# Sheet1.net
KiCad netlist of a schematic drawn in Altium Designer
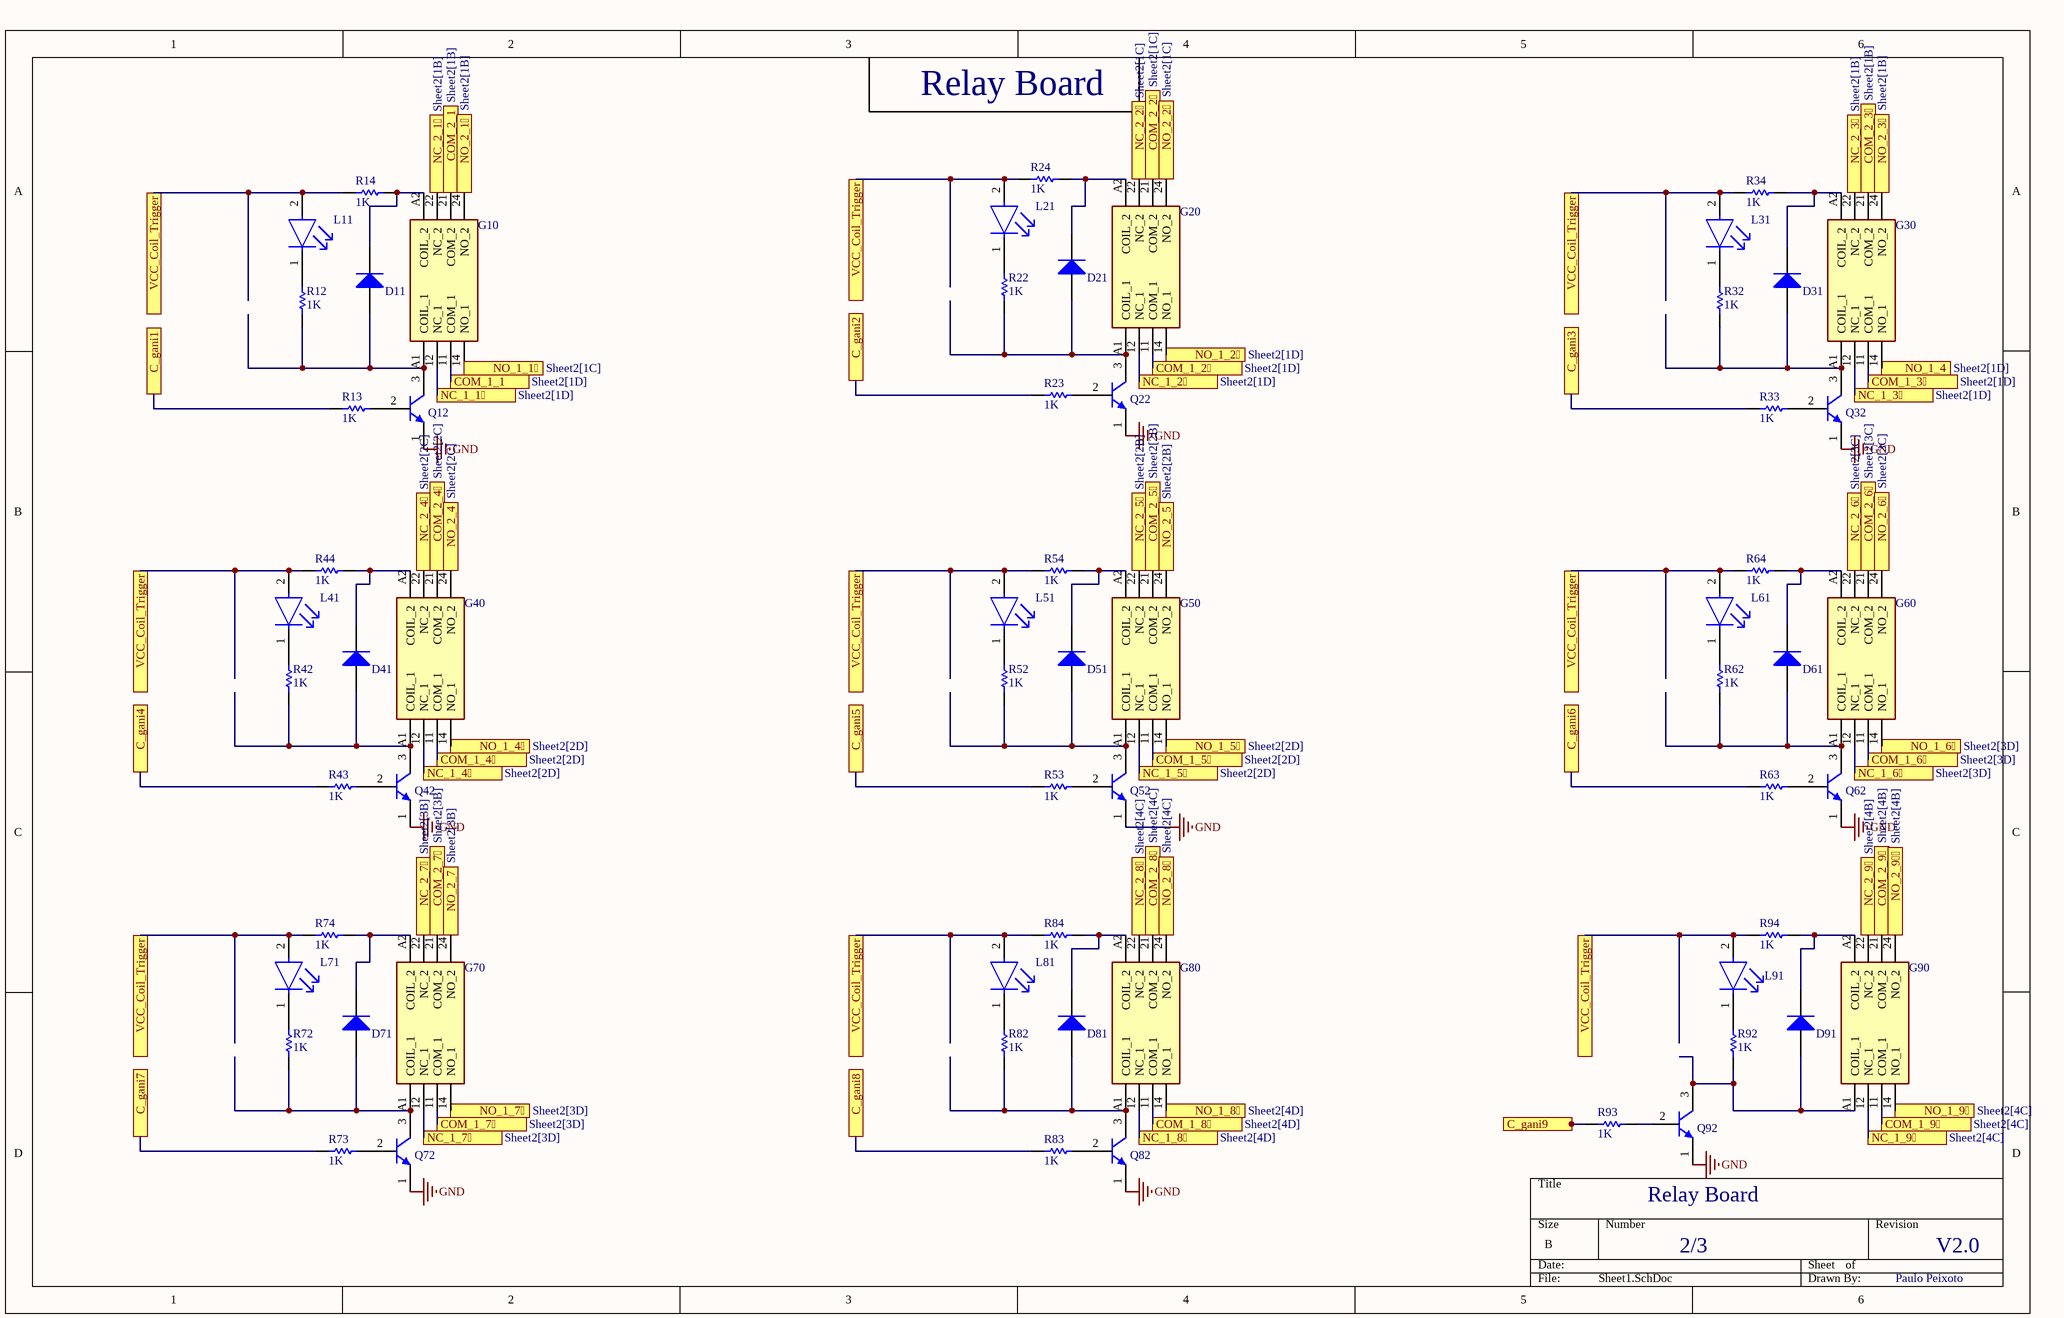
[diagram p0: Sheet1.SchDoc]

(export (version "E")
  (design (tool "Eeschema 10.0.6"))
  (components
    (comp (ref "D11")
      (value "1N4001-T")
      (footprint "DIOD-DO-41-P-2_V")
      (description "1.0 A Rectifier, 15 pF, 50 V, -65 to 150 degC, 2-Pin DO-41 Plastic, RoHS, Tape and Reel")
      (fields (field (name "MANUFACTURER") "Diodes Inc"))
      (libsource (lib "Altium Content Vault") (part "DIOD-D-A1K2-2"))
    )
    (comp (ref "D21")
      (value "1N4001-T")
      (footprint "DIOD-DO-41-P-2_V")
      (description "1.0 A Rectifier, 15 pF, 50 V, -65 to 150 degC, 2-Pin DO-41 Plastic, RoHS, Tape and Reel")
      (fields (field (name "MANUFACTURER") "Diodes Inc"))
      (libsource (lib "Altium Content Vault") (part "DIOD-D-A1K2-2"))
    )
    (comp (ref "D31")
      (value "1N4001-T")
      (footprint "DIOD-DO-41-P-2_V")
      (description "1.0 A Rectifier, 15 pF, 50 V, -65 to 150 degC, 2-Pin DO-41 Plastic, RoHS, Tape and Reel")
      (fields (field (name "MANUFACTURER") "Diodes Inc"))
      (libsource (lib "Altium Content Vault") (part "DIOD-D-A1K2-2"))
    )
    (comp (ref "D41")
      (value "1N4001-T")
      (footprint "DIOD-DO-41-P-2_V")
      (description "1.0 A Rectifier, 15 pF, 50 V, -65 to 150 degC, 2-Pin DO-41 Plastic, RoHS, Tape and Reel")
      (fields (field (name "MANUFACTURER") "Diodes Inc"))
      (libsource (lib "Altium Content Vault") (part "DIOD-D-A1K2-2"))
    )
    (comp (ref "D51")
      (value "1N4001-T")
      (footprint "DIOD-DO-41-P-2_V")
      (description "1.0 A Rectifier, 15 pF, 50 V, -65 to 150 degC, 2-Pin DO-41 Plastic, RoHS, Tape and Reel")
      (fields (field (name "MANUFACTURER") "Diodes Inc"))
      (libsource (lib "Altium Content Vault") (part "DIOD-D-A1K2-2"))
    )
    (comp (ref "D61")
      (value "1N4001-T")
      (footprint "DIOD-DO-41-P-2_V")
      (description "1.0 A Rectifier, 15 pF, 50 V, -65 to 150 degC, 2-Pin DO-41 Plastic, RoHS, Tape and Reel")
      (fields (field (name "MANUFACTURER") "Diodes Inc"))
      (libsource (lib "Altium Content Vault") (part "DIOD-D-A1K2-2"))
    )
    (comp (ref "D71")
      (value "1N4001-T")
      (footprint "DIOD-DO-41-P-2_V")
      (description "1.0 A Rectifier, 15 pF, 50 V, -65 to 150 degC, 2-Pin DO-41 Plastic, RoHS, Tape and Reel")
      (fields (field (name "MANUFACTURER") "Diodes Inc"))
      (libsource (lib "Altium Content Vault") (part "DIOD-D-A1K2-2"))
    )
    (comp (ref "D81")
      (value "1N4001-T")
      (footprint "DIOD-DO-41-P-2_V")
      (description "1.0 A Rectifier, 15 pF, 50 V, -65 to 150 degC, 2-Pin DO-41 Plastic, RoHS, Tape and Reel")
      (fields (field (name "MANUFACTURER") "Diodes Inc"))
      (libsource (lib "Altium Content Vault") (part "DIOD-D-A1K2-2"))
    )
    (comp (ref "D91")
      (value "1N4001-T")
      (footprint "DIOD-DO-41-P-2_V")
      (description "1.0 A Rectifier, 15 pF, 50 V, -65 to 150 degC, 2-Pin DO-41 Plastic, RoHS, Tape and Reel")
      (fields (field (name "MANUFACTURER") "Diodes Inc"))
      (libsource (lib "Altium Content Vault") (part "DIOD-D-A1K2-2"))
    )
    (comp (ref "G10")
      (value "40.52.9.012.0000")
      (footprint "405290120000")
      (description "Relay or Contactor")
      (libsource (lib "GEPE_SchLib_Altium") (part "Relay 40.52.9.012.0000"))
    )
    (comp (ref "G20")
      (value "40.52.9.012.0000")
      (footprint "405290120000")
      (description "Relay or Contactor")
      (libsource (lib "GEPE_SchLib_Altium") (part "Relay 40.52.9.012.0000"))
    )
    (comp (ref "G30")
      (value "40.52.9.012.0000")
      (footprint "405290120000")
      (description "Relay or Contactor")
      (libsource (lib "GEPE_SchLib_Altium") (part "Relay 40.52.9.012.0000"))
    )
    (comp (ref "G40")
      (value "40.52.9.012.0000")
      (footprint "405290120000")
      (description "Relay or Contactor")
      (libsource (lib "GEPE_SchLib_Altium") (part "Relay 40.52.9.012.0000"))
    )
    (comp (ref "G50")
      (value "40.52.9.012.0000")
      (footprint "405290120000")
      (description "Relay or Contactor")
      (libsource (lib "GEPE_SchLib_Altium") (part "Relay 40.52.9.012.0000"))
    )
    (comp (ref "G60")
      (value "40.52.9.012.0000")
      (footprint "405290120000")
      (description "Relay or Contactor")
      (libsource (lib "GEPE_SchLib_Altium") (part "Relay 40.52.9.012.0000"))
    )
    (comp (ref "G70")
      (value "40.52.9.012.0000")
      (footprint "405290120000")
      (description "Relay or Contactor")
      (libsource (lib "GEPE_SchLib_Altium") (part "Relay 40.52.9.012.0000"))
    )
    (comp (ref "G80")
      (value "40.52.9.012.0000")
      (footprint "405290120000")
      (description "Relay or Contactor")
      (libsource (lib "GEPE_SchLib_Altium") (part "Relay 40.52.9.012.0000"))
    )
    (comp (ref "G90")
      (value "40.52.9.012.0000")
      (footprint "405290120000")
      (description "Relay or Contactor")
      (libsource (lib "GEPE_SchLib_Altium") (part "Relay 40.52.9.012.0000"))
    )
    (comp (ref "L11")
      (value "TLLG4400")
      (footprint "FP-6_544-5255_01-4-MFG")
      (description "TLLG4400 Led, Pcb, Green, 0.63MCD, 3MM, T-1, 7MA, 1.9V, 565NM, 25DEG, 20V, 20MW, -40")
      (libsource (lib "Altium Content Vault") (part "8706943c75ba83719d021d2fdc84c58"))
    )
    (comp (ref "L21")
      (value "TLLG4400")
      (footprint "FP-6_544-5255_01-4-MFG")
      (description "TLLG4400 Led, Pcb, Green, 0.63MCD, 3MM, T-1, 7MA, 1.9V, 565NM, 25DEG, 20V, 20MW, -40")
      (libsource (lib "Altium Content Vault") (part "8706943c75ba83719d021d2fdc84c58"))
    )
    (comp (ref "L31")
      (value "TLLG4400")
      (footprint "FP-6_544-5255_01-4-MFG")
      (description "TLLG4400 Led, Pcb, Green, 0.63MCD, 3MM, T-1, 7MA, 1.9V, 565NM, 25DEG, 20V, 20MW, -40")
      (libsource (lib "Altium Content Vault") (part "8706943c75ba83719d021d2fdc84c58"))
    )
    (comp (ref "L41")
      (value "TLLG4400")
      (footprint "FP-6_544-5255_01-4-MFG")
      (description "TLLG4400 Led, Pcb, Green, 0.63MCD, 3MM, T-1, 7MA, 1.9V, 565NM, 25DEG, 20V, 20MW, -40")
      (libsource (lib "Altium Content Vault") (part "8706943c75ba83719d021d2fdc84c58"))
    )
    (comp (ref "L51")
      (value "TLLG4400")
      (footprint "FP-6_544-5255_01-4-MFG")
      (description "TLLG4400 Led, Pcb, Green, 0.63MCD, 3MM, T-1, 7MA, 1.9V, 565NM, 25DEG, 20V, 20MW, -40")
      (libsource (lib "Altium Content Vault") (part "8706943c75ba83719d021d2fdc84c58"))
    )
    (comp (ref "L61")
      (value "TLLG4400")
      (footprint "FP-6_544-5255_01-4-MFG")
      (description "TLLG4400 Led, Pcb, Green, 0.63MCD, 3MM, T-1, 7MA, 1.9V, 565NM, 25DEG, 20V, 20MW, -40")
      (libsource (lib "Altium Content Vault") (part "8706943c75ba83719d021d2fdc84c58"))
    )
    (comp (ref "L71")
      (value "TLLG4400")
      (footprint "FP-6_544-5255_01-4-MFG")
      (description "TLLG4400 Led, Pcb, Green, 0.63MCD, 3MM, T-1, 7MA, 1.9V, 565NM, 25DEG, 20V, 20MW, -40")
      (libsource (lib "Altium Content Vault") (part "8706943c75ba83719d021d2fdc84c58"))
    )
    (comp (ref "L81")
      (value "TLLG4400")
      (footprint "FP-6_544-5255_01-4-MFG")
      (description "TLLG4400 Led, Pcb, Green, 0.63MCD, 3MM, T-1, 7MA, 1.9V, 565NM, 25DEG, 20V, 20MW, -40")
      (libsource (lib "Altium Content Vault") (part "8706943c75ba83719d021d2fdc84c58"))
    )
    (comp (ref "L91")
      (value "TLLG4400")
      (footprint "FP-6_544-5255_01-4-MFG")
      (description "TLLG4400 Led, Pcb, Green, 0.63MCD, 3MM, T-1, 7MA, 1.9V, 565NM, 25DEG, 20V, 20MW, -40")
      (libsource (lib "Altium Content Vault") (part "8706943c75ba83719d021d2fdc84c58"))
    )
    (comp (ref "Q12")
      (value "PN2222ATF")
      (footprint "FAIR-TO-92-3")
      (description "NPN General-Purpose Amplifier, 40 V, -55 to 150 degC, 3-Pin TO-92, RoHS, Tape and Reel")
      (fields (field (name "MANUFACTURER") "FairchildSemiconductor"))
      (libsource (lib "Altium Content Vault") (part "BJT-NPN-EBC-3"))
    )
    (comp (ref "Q22")
      (value "PN2222ATF")
      (footprint "FAIR-TO-92-3")
      (description "NPN General-Purpose Amplifier, 40 V, -55 to 150 degC, 3-Pin TO-92, RoHS, Tape and Reel")
      (fields (field (name "MANUFACTURER") "FairchildSemiconductor"))
      (libsource (lib "Altium Content Vault") (part "BJT-NPN-EBC-3"))
    )
    (comp (ref "Q32")
      (value "PN2222ATF")
      (footprint "FAIR-TO-92-3")
      (description "NPN General-Purpose Amplifier, 40 V, -55 to 150 degC, 3-Pin TO-92, RoHS, Tape and Reel")
      (fields (field (name "MANUFACTURER") "FairchildSemiconductor"))
      (libsource (lib "Altium Content Vault") (part "BJT-NPN-EBC-3"))
    )
    (comp (ref "Q42")
      (value "PN2222ATF")
      (footprint "FAIR-TO-92-3")
      (description "NPN General-Purpose Amplifier, 40 V, -55 to 150 degC, 3-Pin TO-92, RoHS, Tape and Reel")
      (fields (field (name "MANUFACTURER") "FairchildSemiconductor"))
      (libsource (lib "Altium Content Vault") (part "BJT-NPN-EBC-3"))
    )
    (comp (ref "Q52")
      (value "PN2222ATF")
      (footprint "FAIR-TO-92-3")
      (description "NPN General-Purpose Amplifier, 40 V, -55 to 150 degC, 3-Pin TO-92, RoHS, Tape and Reel")
      (fields (field (name "MANUFACTURER") "FairchildSemiconductor"))
      (libsource (lib "Altium Content Vault") (part "BJT-NPN-EBC-3"))
    )
    (comp (ref "Q62")
      (value "PN2222ATF")
      (footprint "FAIR-TO-92-3")
      (description "NPN General-Purpose Amplifier, 40 V, -55 to 150 degC, 3-Pin TO-92, RoHS, Tape and Reel")
      (fields (field (name "MANUFACTURER") "FairchildSemiconductor"))
      (libsource (lib "Altium Content Vault") (part "BJT-NPN-EBC-3"))
    )
    (comp (ref "Q72")
      (value "PN2222ATF")
      (footprint "FAIR-TO-92-3")
      (description "NPN General-Purpose Amplifier, 40 V, -55 to 150 degC, 3-Pin TO-92, RoHS, Tape and Reel")
      (fields (field (name "MANUFACTURER") "FairchildSemiconductor"))
      (libsource (lib "Altium Content Vault") (part "BJT-NPN-EBC-3"))
    )
    (comp (ref "Q82")
      (value "PN2222ATF")
      (footprint "FAIR-TO-92-3")
      (description "NPN General-Purpose Amplifier, 40 V, -55 to 150 degC, 3-Pin TO-92, RoHS, Tape and Reel")
      (fields (field (name "MANUFACTURER") "FairchildSemiconductor"))
      (libsource (lib "Altium Content Vault") (part "BJT-NPN-EBC-3"))
    )
    (comp (ref "Q92")
      (value "PN2222ATF")
      (footprint "FAIR-TO-92-3")
      (description "NPN General-Purpose Amplifier, 40 V, -55 to 150 degC, 3-Pin TO-92, RoHS, Tape and Reel")
      (fields (field (name "MANUFACTURER") "FairchildSemiconductor"))
      (libsource (lib "Altium Content Vault") (part "BJT-NPN-EBC-3"))
    )
    (comp (ref "R12")
      (value "1K")
      (footprint "RESC3216X70X50NL05T20")
      (fields (field (name "MANUFACTURER") "Panasonic") (field (name "PART NUMBER") "ERJ-8GEY0R00V"))
      (libsource (lib "Altium Content Vault") (part "RES"))
    )
    (comp (ref "R13")
      (value "1K")
      (footprint "RESC3216X70X50NL05T20")
      (fields (field (name "MANUFACTURER") "Panasonic") (field (name "PART NUMBER") "ERJ-8GEY0R00V"))
      (libsource (lib "Altium Content Vault") (part "RES"))
    )
    (comp (ref "R14")
      (value "1K")
      (footprint "RESC3216X70X50NL05T20")
      (fields (field (name "MANUFACTURER") "Panasonic") (field (name "PART NUMBER") "ERJ-8GEY0R00V"))
      (libsource (lib "Altium Content Vault") (part "RES"))
    )
    (comp (ref "R22")
      (value "1K")
      (footprint "RESC3216X70X50NL05T20")
      (fields (field (name "MANUFACTURER") "Panasonic") (field (name "PART NUMBER") "ERJ-8GEY0R00V"))
      (libsource (lib "Altium Content Vault") (part "RES"))
    )
    (comp (ref "R23")
      (value "1K")
      (footprint "RESC3216X70X50NL05T20")
      (fields (field (name "MANUFACTURER") "Panasonic") (field (name "PART NUMBER") "ERJ-8GEY0R00V"))
      (libsource (lib "Altium Content Vault") (part "RES"))
    )
    (comp (ref "R24")
      (value "1K")
      (footprint "RESC3216X70X50NL05T20")
      (fields (field (name "MANUFACTURER") "Panasonic") (field (name "PART NUMBER") "ERJ-8GEY0R00V"))
      (libsource (lib "Altium Content Vault") (part "RES"))
    )
    (comp (ref "R32")
      (value "1K")
      (footprint "RESC3216X70X50NL05T20")
      (fields (field (name "MANUFACTURER") "Panasonic") (field (name "PART NUMBER") "ERJ-8GEY0R00V"))
      (libsource (lib "Altium Content Vault") (part "RES"))
    )
    (comp (ref "R33")
      (value "1K")
      (footprint "RESC3216X70X50NL05T20")
      (fields (field (name "MANUFACTURER") "Panasonic") (field (name "PART NUMBER") "ERJ-8GEY0R00V"))
      (libsource (lib "Altium Content Vault") (part "RES"))
    )
    (comp (ref "R34")
      (value "1K")
      (footprint "RESC3216X70X50NL05T20")
      (fields (field (name "MANUFACTURER") "Panasonic") (field (name "PART NUMBER") "ERJ-8GEY0R00V"))
      (libsource (lib "Altium Content Vault") (part "RES"))
    )
    (comp (ref "R42")
      (value "1K")
      (footprint "RESC3216X70X50NL05T20")
      (fields (field (name "MANUFACTURER") "Panasonic") (field (name "PART NUMBER") "ERJ-8GEY0R00V"))
      (libsource (lib "Altium Content Vault") (part "RES"))
    )
    (comp (ref "R43")
      (value "1K")
      (footprint "RESC3216X70X50NL05T20")
      (fields (field (name "MANUFACTURER") "Panasonic") (field (name "PART NUMBER") "ERJ-8GEY0R00V"))
      (libsource (lib "Altium Content Vault") (part "RES"))
    )
    (comp (ref "R44")
      (value "1K")
      (footprint "RESC3216X70X50NL05T20")
      (fields (field (name "MANUFACTURER") "Panasonic") (field (name "PART NUMBER") "ERJ-8GEY0R00V"))
      (libsource (lib "Altium Content Vault") (part "RES"))
    )
    (comp (ref "R52")
      (value "1K")
      (footprint "RESC3216X70X50NL05T20")
      (fields (field (name "MANUFACTURER") "Panasonic") (field (name "PART NUMBER") "ERJ-8GEY0R00V"))
      (libsource (lib "Altium Content Vault") (part "RES"))
    )
    (comp (ref "R53")
      (value "1K")
      (footprint "RESC3216X70X50NL05T20")
      (fields (field (name "MANUFACTURER") "Panasonic") (field (name "PART NUMBER") "ERJ-8GEY0R00V"))
      (libsource (lib "Altium Content Vault") (part "RES"))
    )
    (comp (ref "R54")
      (value "1K")
      (footprint "RESC3216X70X50NL05T20")
      (fields (field (name "MANUFACTURER") "Panasonic") (field (name "PART NUMBER") "ERJ-8GEY0R00V"))
      (libsource (lib "Altium Content Vault") (part "RES"))
    )
    (comp (ref "R62")
      (value "1K")
      (footprint "RESC3216X70X50NL05T20")
      (fields (field (name "MANUFACTURER") "Panasonic") (field (name "PART NUMBER") "ERJ-8GEY0R00V"))
      (libsource (lib "Altium Content Vault") (part "RES"))
    )
    (comp (ref "R63")
      (value "1K")
      (footprint "RESC3216X70X50NL05T20")
      (fields (field (name "MANUFACTURER") "Panasonic") (field (name "PART NUMBER") "ERJ-8GEY0R00V"))
      (libsource (lib "Altium Content Vault") (part "RES"))
    )
    (comp (ref "R64")
      (value "1K")
      (footprint "RESC3216X70X50NL05T20")
      (fields (field (name "MANUFACTURER") "Panasonic") (field (name "PART NUMBER") "ERJ-8GEY0R00V"))
      (libsource (lib "Altium Content Vault") (part "RES"))
    )
    (comp (ref "R72")
      (value "1K")
      (footprint "RESC3216X70X50NL05T20")
      (fields (field (name "MANUFACTURER") "Panasonic") (field (name "PART NUMBER") "ERJ-8GEY0R00V"))
      (libsource (lib "Altium Content Vault") (part "RES"))
    )
    (comp (ref "R73")
      (value "1K")
      (footprint "RESC3216X70X50NL05T20")
      (fields (field (name "MANUFACTURER") "Panasonic") (field (name "PART NUMBER") "ERJ-8GEY0R00V"))
      (libsource (lib "Altium Content Vault") (part "RES"))
    )
    (comp (ref "R74")
      (value "1K")
      (footprint "RESC3216X70X50NL05T20")
      (fields (field (name "MANUFACTURER") "Panasonic") (field (name "PART NUMBER") "ERJ-8GEY0R00V"))
      (libsource (lib "Altium Content Vault") (part "RES"))
    )
    (comp (ref "R82")
      (value "1K")
      (footprint "RESC3216X70X50NL05T20")
      (fields (field (name "MANUFACTURER") "Panasonic") (field (name "PART NUMBER") "ERJ-8GEY0R00V"))
      (libsource (lib "Altium Content Vault") (part "RES"))
    )
    (comp (ref "R83")
      (value "1K")
      (footprint "RESC3216X70X50NL05T20")
      (fields (field (name "MANUFACTURER") "Panasonic") (field (name "PART NUMBER") "ERJ-8GEY0R00V"))
      (libsource (lib "Altium Content Vault") (part "RES"))
    )
    (comp (ref "R84")
      (value "1K")
      (footprint "RESC3216X70X50NL05T20")
      (fields (field (name "MANUFACTURER") "Panasonic") (field (name "PART NUMBER") "ERJ-8GEY0R00V"))
      (libsource (lib "Altium Content Vault") (part "RES"))
    )
    (comp (ref "R92")
      (value "1K")
      (footprint "RESC3216X70X50NL05T20")
      (fields (field (name "MANUFACTURER") "Panasonic") (field (name "PART NUMBER") "ERJ-8GEY0R00V"))
      (libsource (lib "Altium Content Vault") (part "RES"))
    )
    (comp (ref "R93")
      (value "1K")
      (footprint "RESC3216X70X50NL05T20")
      (fields (field (name "MANUFACTURER") "Panasonic") (field (name "PART NUMBER") "ERJ-8GEY0R00V"))
      (libsource (lib "Altium Content Vault") (part "RES"))
    )
    (comp (ref "R94")
      (value "1K")
      (footprint "RESC3216X70X50NL05T20")
      (fields (field (name "MANUFACTURER") "Panasonic") (field (name "PART NUMBER") "ERJ-8GEY0R00V"))
      (libsource (lib "Altium Content Vault") (part "RES"))
    )
  )
  (nets
    (net (code "1") (name "/COM_1_1") (class "Default")
      (node (ref "G10") (pin "11") (pinfunction "COM_1_11") (pintype "passive"))
    )
    (net (code "2") (name "/COM_1_2") (class "Default")
      (node (ref "G20") (pin "11") (pinfunction "COM_1_11") (pintype "passive"))
    )
    (net (code "3") (name "/COM_1_3") (class "Default")
      (node (ref "G30") (pin "11") (pinfunction "COM_1_11") (pintype "passive"))
    )
    (net (code "4") (name "/COM_1_4") (class "Default")
      (node (ref "G40") (pin "11") (pinfunction "COM_1_11") (pintype "passive"))
    )
    (net (code "5") (name "/COM_1_5") (class "Default")
      (node (ref "G50") (pin "11") (pinfunction "COM_1_11") (pintype "passive"))
    )
    (net (code "6") (name "/COM_1_6") (class "Default")
      (node (ref "G60") (pin "11") (pinfunction "COM_1_11") (pintype "passive"))
    )
    (net (code "7") (name "/COM_1_7") (class "Default")
      (node (ref "G70") (pin "11") (pinfunction "COM_1_11") (pintype "passive"))
    )
    (net (code "8") (name "/COM_1_8") (class "Default")
      (node (ref "G80") (pin "11") (pinfunction "COM_1_11") (pintype "passive"))
    )
    (net (code "9") (name "/COM_1_9") (class "Default")
      (node (ref "G90") (pin "11") (pinfunction "COM_1_11") (pintype "passive"))
    )
    (net (code "19") (name "/COM_2_1") (class "Default")
      (node (ref "G10") (pin "21") (pinfunction "COM_2_21") (pintype "passive"))
    )
    (net (code "20") (name "/C_gani1") (class "Default")
      (node (ref "R13") (pin "2") (pinfunction "2_2") (pintype "passive"))
    )
    (net (code "21") (name "/C_gani2") (class "Default")
      (node (ref "R23") (pin "2") (pinfunction "2_2") (pintype "passive"))
    )
    (net (code "22") (name "/C_gani3") (class "Default")
      (node (ref "R33") (pin "2") (pinfunction "2_2") (pintype "passive"))
    )
    (net (code "23") (name "/C_gani4") (class "Default")
      (node (ref "R43") (pin "2") (pinfunction "2_2") (pintype "passive"))
    )
    (net (code "24") (name "/C_gani5") (class "Default")
      (node (ref "R53") (pin "2") (pinfunction "2_2") (pintype "passive"))
    )
    (net (code "25") (name "/C_gani6") (class "Default")
      (node (ref "R63") (pin "2") (pinfunction "2_2") (pintype "passive"))
    )
    (net (code "26") (name "/C_gani7") (class "Default")
      (node (ref "R73") (pin "2") (pinfunction "2_2") (pintype "passive"))
    )
    (net (code "27") (name "/C_gani8") (class "Default")
      (node (ref "R83") (pin "2") (pinfunction "2_2") (pintype "passive"))
    )
    (net (code "28") (name "/C_gani9") (class "Default")
      (node (ref "R93") (pin "2") (pinfunction "2_2") (pintype "passive"))
    )
    (net (code "29") (name "/NC_1_1") (class "Default")
      (node (ref "G10") (pin "12") (pinfunction "NC_1_12") (pintype "passive"))
    )
    (net (code "30") (name "/NC_1_2") (class "Default")
      (node (ref "G20") (pin "12") (pinfunction "NC_1_12") (pintype "passive"))
    )
    (net (code "31") (name "/NC_1_3") (class "Default")
      (node (ref "G30") (pin "12") (pinfunction "NC_1_12") (pintype "passive"))
    )
    (net (code "32") (name "/NC_1_4") (class "Default")
      (node (ref "G40") (pin "12") (pinfunction "NC_1_12") (pintype "passive"))
    )
    (net (code "33") (name "/NC_1_5") (class "Default")
      (node (ref "G50") (pin "12") (pinfunction "NC_1_12") (pintype "passive"))
    )
    (net (code "34") (name "/NC_1_6") (class "Default")
      (node (ref "G60") (pin "12") (pinfunction "NC_1_12") (pintype "passive"))
    )
    (net (code "35") (name "/NC_1_7") (class "Default")
      (node (ref "G70") (pin "12") (pinfunction "NC_1_12") (pintype "passive"))
    )
    (net (code "36") (name "/NC_1_8") (class "Default")
      (node (ref "G80") (pin "12") (pinfunction "NC_1_12") (pintype "passive"))
    )
    (net (code "64") (name "/NC_1_9") (class "Default")
      (node (ref "G90") (pin "12") (pinfunction "NC_1_12") (pintype "passive"))
    )
    (net (code "65") (name "/NO_1_4") (class "Default")
      (node (ref "G30") (pin "14") (pinfunction "NO_1_14") (pintype "passive"))
    )
    (net (code "66") (name "/NO_2_4") (class "Default")
      (node (ref "G40") (pin "24") (pinfunction "NO_2_24") (pintype "passive"))
    )
    (net (code "67") (name "/NO_2_5") (class "Default")
      (node (ref "G50") (pin "24") (pinfunction "NO_2_24") (pintype "passive"))
    )
    (net (code "68") (name "/NO_2_7") (class "Default")
      (node (ref "G70") (pin "24") (pinfunction "NO_2_24") (pintype "passive"))
    )
    (net (code "69") (name "/VCC_Coil_Trigger") (class "Default")
      (node (ref "L11") (pin "2") (pinfunction "A_2") (pintype "passive"))
      (node (ref "L21") (pin "2") (pinfunction "A_2") (pintype "passive"))
      (node (ref "L31") (pin "2") (pinfunction "A_2") (pintype "passive"))
      (node (ref "L41") (pin "2") (pinfunction "A_2") (pintype "passive"))
      (node (ref "L51") (pin "2") (pinfunction "A_2") (pintype "passive"))
      (node (ref "L61") (pin "2") (pinfunction "A_2") (pintype "passive"))
      (node (ref "L71") (pin "2") (pinfunction "A_2") (pintype "passive"))
      (node (ref "L81") (pin "2") (pinfunction "A_2") (pintype "passive"))
      (node (ref "L91") (pin "2") (pinfunction "A_2") (pintype "passive"))
      (node (ref "R14") (pin "1") (pinfunction "1_1") (pintype "passive"))
      (node (ref "R24") (pin "1") (pinfunction "1_1") (pintype "passive"))
      (node (ref "R34") (pin "1") (pinfunction "1_1") (pintype "passive"))
      (node (ref "R44") (pin "1") (pinfunction "1_1") (pintype "passive"))
      (node (ref "R54") (pin "1") (pinfunction "1_1") (pintype "passive"))
      (node (ref "R64") (pin "1") (pinfunction "1_1") (pintype "passive"))
      (node (ref "R74") (pin "1") (pinfunction "1_1") (pintype "passive"))
      (node (ref "R84") (pin "1") (pinfunction "1_1") (pintype "passive"))
      (node (ref "R94") (pin "1") (pinfunction "1_1") (pintype "passive"))
    )
    (net (code "70") (name "GND") (class "Default")
      (node (ref "Q12") (pin "1") (pinfunction "E_1") (pintype "passive"))
      (node (ref "Q22") (pin "1") (pinfunction "E_1") (pintype "passive"))
      (node (ref "Q32") (pin "1") (pinfunction "E_1") (pintype "passive"))
      (node (ref "Q42") (pin "1") (pinfunction "E_1") (pintype "passive"))
      (node (ref "Q52") (pin "1") (pinfunction "E_1") (pintype "passive"))
      (node (ref "Q62") (pin "1") (pinfunction "E_1") (pintype "passive"))
      (node (ref "Q72") (pin "1") (pinfunction "E_1") (pintype "passive"))
      (node (ref "Q82") (pin "1") (pinfunction "E_1") (pintype "passive"))
      (node (ref "Q92") (pin "1") (pinfunction "E_1") (pintype "passive"))
    )
    (net (code "71") (name "Net-(D11-A)") (class "Default")
      (node (ref "D11") (pin "1") (pinfunction "A_1") (pintype "passive"))
      (node (ref "G10") (pin "A1") (pinfunction "COIL_1_A1") (pintype "passive"))
      (node (ref "Q12") (pin "3") (pinfunction "C_3") (pintype "passive"))
      (node (ref "R12") (pin "1") (pinfunction "1_1") (pintype "passive"))
    )
    (net (code "72") (name "Net-(D11-K)") (class "Default")
      (node (ref "D11") (pin "2") (pinfunction "K_2") (pintype "passive"))
      (node (ref "G10") (pin "A2") (pinfunction "COIL_2_A2") (pintype "passive"))
      (node (ref "R14") (pin "2") (pinfunction "2_2") (pintype "passive"))
    )
    (net (code "73") (name "Net-(D21-A)") (class "Default")
      (node (ref "D21") (pin "1") (pinfunction "A_1") (pintype "passive"))
      (node (ref "G20") (pin "A1") (pinfunction "COIL_1_A1") (pintype "passive"))
      (node (ref "Q22") (pin "3") (pinfunction "C_3") (pintype "passive"))
      (node (ref "R22") (pin "1") (pinfunction "1_1") (pintype "passive"))
    )
    (net (code "74") (name "Net-(D21-K)") (class "Default")
      (node (ref "D21") (pin "2") (pinfunction "K_2") (pintype "passive"))
      (node (ref "G20") (pin "A2") (pinfunction "COIL_2_A2") (pintype "passive"))
      (node (ref "R24") (pin "2") (pinfunction "2_2") (pintype "passive"))
    )
    (net (code "75") (name "Net-(D31-A)") (class "Default")
      (node (ref "D31") (pin "1") (pinfunction "A_1") (pintype "passive"))
      (node (ref "G30") (pin "A1") (pinfunction "COIL_1_A1") (pintype "passive"))
      (node (ref "Q32") (pin "3") (pinfunction "C_3") (pintype "passive"))
      (node (ref "R32") (pin "1") (pinfunction "1_1") (pintype "passive"))
    )
    (net (code "76") (name "Net-(D31-K)") (class "Default")
      (node (ref "D31") (pin "2") (pinfunction "K_2") (pintype "passive"))
      (node (ref "G30") (pin "A2") (pinfunction "COIL_2_A2") (pintype "passive"))
      (node (ref "R34") (pin "2") (pinfunction "2_2") (pintype "passive"))
    )
    (net (code "77") (name "Net-(D41-A)") (class "Default")
      (node (ref "D41") (pin "1") (pinfunction "A_1") (pintype "passive"))
      (node (ref "G40") (pin "A1") (pinfunction "COIL_1_A1") (pintype "passive"))
      (node (ref "Q42") (pin "3") (pinfunction "C_3") (pintype "passive"))
      (node (ref "R42") (pin "1") (pinfunction "1_1") (pintype "passive"))
    )
    (net (code "78") (name "Net-(D41-K)") (class "Default")
      (node (ref "D41") (pin "2") (pinfunction "K_2") (pintype "passive"))
      (node (ref "G40") (pin "A2") (pinfunction "COIL_2_A2") (pintype "passive"))
      (node (ref "R44") (pin "2") (pinfunction "2_2") (pintype "passive"))
    )
    (net (code "79") (name "Net-(D51-A)") (class "Default")
      (node (ref "D51") (pin "1") (pinfunction "A_1") (pintype "passive"))
      (node (ref "G50") (pin "A1") (pinfunction "COIL_1_A1") (pintype "passive"))
      (node (ref "Q52") (pin "3") (pinfunction "C_3") (pintype "passive"))
      (node (ref "R52") (pin "1") (pinfunction "1_1") (pintype "passive"))
    )
    (net (code "80") (name "Net-(D51-K)") (class "Default")
      (node (ref "D51") (pin "2") (pinfunction "K_2") (pintype "passive"))
      (node (ref "G50") (pin "A2") (pinfunction "COIL_2_A2") (pintype "passive"))
      (node (ref "R54") (pin "2") (pinfunction "2_2") (pintype "passive"))
    )
    (net (code "81") (name "Net-(D61-A)") (class "Default")
      (node (ref "D61") (pin "1") (pinfunction "A_1") (pintype "passive"))
      (node (ref "G60") (pin "A1") (pinfunction "COIL_1_A1") (pintype "passive"))
      (node (ref "Q62") (pin "3") (pinfunction "C_3") (pintype "passive"))
      (node (ref "R62") (pin "1") (pinfunction "1_1") (pintype "passive"))
    )
    (net (code "82") (name "Net-(D61-K)") (class "Default")
      (node (ref "D61") (pin "2") (pinfunction "K_2") (pintype "passive"))
      (node (ref "G60") (pin "A2") (pinfunction "COIL_2_A2") (pintype "passive"))
      (node (ref "R64") (pin "2") (pinfunction "2_2") (pintype "passive"))
    )
    (net (code "83") (name "Net-(D71-A)") (class "Default")
      (node (ref "D71") (pin "1") (pinfunction "A_1") (pintype "passive"))
      (node (ref "G70") (pin "A1") (pinfunction "COIL_1_A1") (pintype "passive"))
      (node (ref "Q72") (pin "3") (pinfunction "C_3") (pintype "passive"))
      (node (ref "R72") (pin "1") (pinfunction "1_1") (pintype "passive"))
    )
    (net (code "84") (name "Net-(D71-K)") (class "Default")
      (node (ref "D71") (pin "2") (pinfunction "K_2") (pintype "passive"))
      (node (ref "G70") (pin "A2") (pinfunction "COIL_2_A2") (pintype "passive"))
      (node (ref "R74") (pin "2") (pinfunction "2_2") (pintype "passive"))
    )
    (net (code "85") (name "Net-(D81-A)") (class "Default")
      (node (ref "D81") (pin "1") (pinfunction "A_1") (pintype "passive"))
      (node (ref "G80") (pin "A1") (pinfunction "COIL_1_A1") (pintype "passive"))
      (node (ref "Q82") (pin "3") (pinfunction "C_3") (pintype "passive"))
      (node (ref "R82") (pin "1") (pinfunction "1_1") (pintype "passive"))
    )
    (net (code "86") (name "Net-(D81-K)") (class "Default")
      (node (ref "D81") (pin "2") (pinfunction "K_2") (pintype "passive"))
      (node (ref "G80") (pin "A2") (pinfunction "COIL_2_A2") (pintype "passive"))
      (node (ref "R84") (pin "2") (pinfunction "2_2") (pintype "passive"))
    )
    (net (code "87") (name "Net-(D91-A)") (class "Default")
      (node (ref "D91") (pin "1") (pinfunction "A_1") (pintype "passive"))
      (node (ref "G90") (pin "A1") (pinfunction "COIL_1_A1") (pintype "passive"))
      (node (ref "Q92") (pin "3") (pinfunction "C_3") (pintype "passive"))
      (node (ref "R92") (pin "1") (pinfunction "1_1") (pintype "passive"))
    )
    (net (code "88") (name "Net-(D91-K)") (class "Default")
      (node (ref "D91") (pin "2") (pinfunction "K_2") (pintype "passive"))
      (node (ref "G90") (pin "A2") (pinfunction "COIL_2_A2") (pintype "passive"))
      (node (ref "R94") (pin "2") (pinfunction "2_2") (pintype "passive"))
    )
    (net (code "89") (name "Net-(L11-C)") (class "Default")
      (node (ref "L11") (pin "1") (pinfunction "C_1") (pintype "passive"))
      (node (ref "R12") (pin "2") (pinfunction "2_2") (pintype "passive"))
    )
    (net (code "90") (name "Net-(L21-C)") (class "Default")
      (node (ref "L21") (pin "1") (pinfunction "C_1") (pintype "passive"))
      (node (ref "R22") (pin "2") (pinfunction "2_2") (pintype "passive"))
    )
    (net (code "91") (name "Net-(L31-C)") (class "Default")
      (node (ref "L31") (pin "1") (pinfunction "C_1") (pintype "passive"))
      (node (ref "R32") (pin "2") (pinfunction "2_2") (pintype "passive"))
    )
    (net (code "92") (name "Net-(L41-C)") (class "Default")
      (node (ref "L41") (pin "1") (pinfunction "C_1") (pintype "passive"))
      (node (ref "R42") (pin "2") (pinfunction "2_2") (pintype "passive"))
    )
    (net (code "93") (name "Net-(L51-C)") (class "Default")
      (node (ref "L51") (pin "1") (pinfunction "C_1") (pintype "passive"))
      (node (ref "R52") (pin "2") (pinfunction "2_2") (pintype "passive"))
    )
    (net (code "94") (name "Net-(L61-C)") (class "Default")
      (node (ref "L61") (pin "1") (pinfunction "C_1") (pintype "passive"))
      (node (ref "R62") (pin "2") (pinfunction "2_2") (pintype "passive"))
    )
    (net (code "95") (name "Net-(L71-C)") (class "Default")
      (node (ref "L71") (pin "1") (pinfunction "C_1") (pintype "passive"))
      (node (ref "R72") (pin "2") (pinfunction "2_2") (pintype "passive"))
    )
    (net (code "96") (name "Net-(L81-C)") (class "Default")
      (node (ref "L81") (pin "1") (pinfunction "C_1") (pintype "passive"))
      (node (ref "R82") (pin "2") (pinfunction "2_2") (pintype "passive"))
    )
    (net (code "97") (name "Net-(L91-C)") (class "Default")
      (node (ref "L91") (pin "1") (pinfunction "C_1") (pintype "passive"))
      (node (ref "R92") (pin "2") (pinfunction "2_2") (pintype "passive"))
    )
    (net (code "98") (name "Net-(Q12-B)") (class "Default")
      (node (ref "Q12") (pin "2") (pinfunction "B_2") (pintype "passive"))
      (node (ref "R13") (pin "1") (pinfunction "1_1") (pintype "passive"))
    )
    (net (code "99") (name "Net-(Q22-B)") (class "Default")
      (node (ref "Q22") (pin "2") (pinfunction "B_2") (pintype "passive"))
      (node (ref "R23") (pin "1") (pinfunction "1_1") (pintype "passive"))
    )
    (net (code "100") (name "Net-(Q32-B)") (class "Default")
      (node (ref "Q32") (pin "2") (pinfunction "B_2") (pintype "passive"))
      (node (ref "R33") (pin "1") (pinfunction "1_1") (pintype "passive"))
    )
    (net (code "101") (name "Net-(Q42-B)") (class "Default")
      (node (ref "Q42") (pin "2") (pinfunction "B_2") (pintype "passive"))
      (node (ref "R43") (pin "1") (pinfunction "1_1") (pintype "passive"))
    )
    (net (code "102") (name "Net-(Q52-B)") (class "Default")
      (node (ref "Q52") (pin "2") (pinfunction "B_2") (pintype "passive"))
      (node (ref "R53") (pin "1") (pinfunction "1_1") (pintype "passive"))
    )
    (net (code "103") (name "Net-(Q62-B)") (class "Default")
      (node (ref "Q62") (pin "2") (pinfunction "B_2") (pintype "passive"))
      (node (ref "R63") (pin "1") (pinfunction "1_1") (pintype "passive"))
    )
    (net (code "104") (name "Net-(Q72-B)") (class "Default")
      (node (ref "Q72") (pin "2") (pinfunction "B_2") (pintype "passive"))
      (node (ref "R73") (pin "1") (pinfunction "1_1") (pintype "passive"))
    )
    (net (code "105") (name "Net-(Q82-B)") (class "Default")
      (node (ref "Q82") (pin "2") (pinfunction "B_2") (pintype "passive"))
      (node (ref "R83") (pin "1") (pinfunction "1_1") (pintype "passive"))
    )
    (net (code "106") (name "Net-(Q92-B)") (class "Default")
      (node (ref "Q92") (pin "2") (pinfunction "B_2") (pintype "passive"))
      (node (ref "R93") (pin "1") (pinfunction "1_1") (pintype "passive"))
    )
    (net (code "107") (name "unconnected-(G10-NC_2-Pad22)") (class "Default")
      (node (ref "G10") (pin "22") (pinfunction "NC_2_22") (pintype "passive"))
    )
    (net (code "108") (name "unconnected-(G10-NO_1-Pad14)") (class "Default")
      (node (ref "G10") (pin "14") (pinfunction "NO_1_14") (pintype "passive"))
    )
    (net (code "109") (name "unconnected-(G10-NO_2-Pad24)") (class "Default")
      (node (ref "G10") (pin "24") (pinfunction "NO_2_24") (pintype "passive"))
    )
    (net (code "110") (name "unconnected-(G20-COM_2-Pad21)") (class "Default")
      (node (ref "G20") (pin "21") (pinfunction "COM_2_21") (pintype "passive"))
    )
    (net (code "111") (name "unconnected-(G20-NC_2-Pad22)") (class "Default")
      (node (ref "G20") (pin "22") (pinfunction "NC_2_22") (pintype "passive"))
    )
    (net (code "112") (name "unconnected-(G20-NO_1-Pad14)") (class "Default")
      (node (ref "G20") (pin "14") (pinfunction "NO_1_14") (pintype "passive"))
    )
    (net (code "113") (name "unconnected-(G20-NO_2-Pad24)") (class "Default")
      (node (ref "G20") (pin "24") (pinfunction "NO_2_24") (pintype "passive"))
    )
    (net (code "114") (name "unconnected-(G30-COM_2-Pad21)") (class "Default")
      (node (ref "G30") (pin "21") (pinfunction "COM_2_21") (pintype "passive"))
    )
    (net (code "115") (name "unconnected-(G30-NC_2-Pad22)") (class "Default")
      (node (ref "G30") (pin "22") (pinfunction "NC_2_22") (pintype "passive"))
    )
    (net (code "116") (name "unconnected-(G30-NO_2-Pad24)") (class "Default")
      (node (ref "G30") (pin "24") (pinfunction "NO_2_24") (pintype "passive"))
    )
    (net (code "117") (name "unconnected-(G40-COM_2-Pad21)") (class "Default")
      (node (ref "G40") (pin "21") (pinfunction "COM_2_21") (pintype "passive"))
    )
    (net (code "118") (name "unconnected-(G40-NC_2-Pad22)") (class "Default")
      (node (ref "G40") (pin "22") (pinfunction "NC_2_22") (pintype "passive"))
    )
    (net (code "119") (name "unconnected-(G40-NO_1-Pad14)") (class "Default")
      (node (ref "G40") (pin "14") (pinfunction "NO_1_14") (pintype "passive"))
    )
    (net (code "120") (name "unconnected-(G50-COM_2-Pad21)") (class "Default")
      (node (ref "G50") (pin "21") (pinfunction "COM_2_21") (pintype "passive"))
    )
    (net (code "121") (name "unconnected-(G50-NC_2-Pad22)") (class "Default")
      (node (ref "G50") (pin "22") (pinfunction "NC_2_22") (pintype "passive"))
    )
    (net (code "122") (name "unconnected-(G50-NO_1-Pad14)") (class "Default")
      (node (ref "G50") (pin "14") (pinfunction "NO_1_14") (pintype "passive"))
    )
    (net (code "123") (name "unconnected-(G60-COM_2-Pad21)") (class "Default")
      (node (ref "G60") (pin "21") (pinfunction "COM_2_21") (pintype "passive"))
    )
    (net (code "124") (name "unconnected-(G60-NC_2-Pad22)") (class "Default")
      (node (ref "G60") (pin "22") (pinfunction "NC_2_22") (pintype "passive"))
    )
    (net (code "125") (name "unconnected-(G60-NO_1-Pad14)") (class "Default")
      (node (ref "G60") (pin "14") (pinfunction "NO_1_14") (pintype "passive"))
    )
    (net (code "126") (name "unconnected-(G60-NO_2-Pad24)") (class "Default")
      (node (ref "G60") (pin "24") (pinfunction "NO_2_24") (pintype "passive"))
    )
    (net (code "127") (name "unconnected-(G70-COM_2-Pad21)") (class "Default")
      (node (ref "G70") (pin "21") (pinfunction "COM_2_21") (pintype "passive"))
    )
    (net (code "128") (name "unconnected-(G70-NC_2-Pad22)") (class "Default")
      (node (ref "G70") (pin "22") (pinfunction "NC_2_22") (pintype "passive"))
    )
    (net (code "129") (name "unconnected-(G70-NO_1-Pad14)") (class "Default")
      (node (ref "G70") (pin "14") (pinfunction "NO_1_14") (pintype "passive"))
    )
    (net (code "130") (name "unconnected-(G80-COM_2-Pad21)") (class "Default")
      (node (ref "G80") (pin "21") (pinfunction "COM_2_21") (pintype "passive"))
    )
    (net (code "131") (name "unconnected-(G80-NC_2-Pad22)") (class "Default")
      (node (ref "G80") (pin "22") (pinfunction "NC_2_22") (pintype "passive"))
    )
    (net (code "132") (name "unconnected-(G80-NO_1-Pad14)") (class "Default")
      (node (ref "G80") (pin "14") (pinfunction "NO_1_14") (pintype "passive"))
    )
    (net (code "133") (name "unconnected-(G80-NO_2-Pad24)") (class "Default")
      (node (ref "G80") (pin "24") (pinfunction "NO_2_24") (pintype "passive"))
    )
    (net (code "134") (name "unconnected-(G90-COM_2-Pad21)") (class "Default")
      (node (ref "G90") (pin "21") (pinfunction "COM_2_21") (pintype "passive"))
    )
    (net (code "135") (name "unconnected-(G90-NC_2-Pad22)") (class "Default")
      (node (ref "G90") (pin "22") (pinfunction "NC_2_22") (pintype "passive"))
    )
    (net (code "136") (name "unconnected-(G90-NO_1-Pad14)") (class "Default")
      (node (ref "G90") (pin "14") (pinfunction "NO_1_14") (pintype "passive"))
    )
    (net (code "137") (name "unconnected-(G90-NO_2-Pad24)") (class "Default")
      (node (ref "G90") (pin "24") (pinfunction "NO_2_24") (pintype "passive"))
    )
  )
)
